# DCC-motor.net
KiCad netlist of a schematic drawn in EAGLE
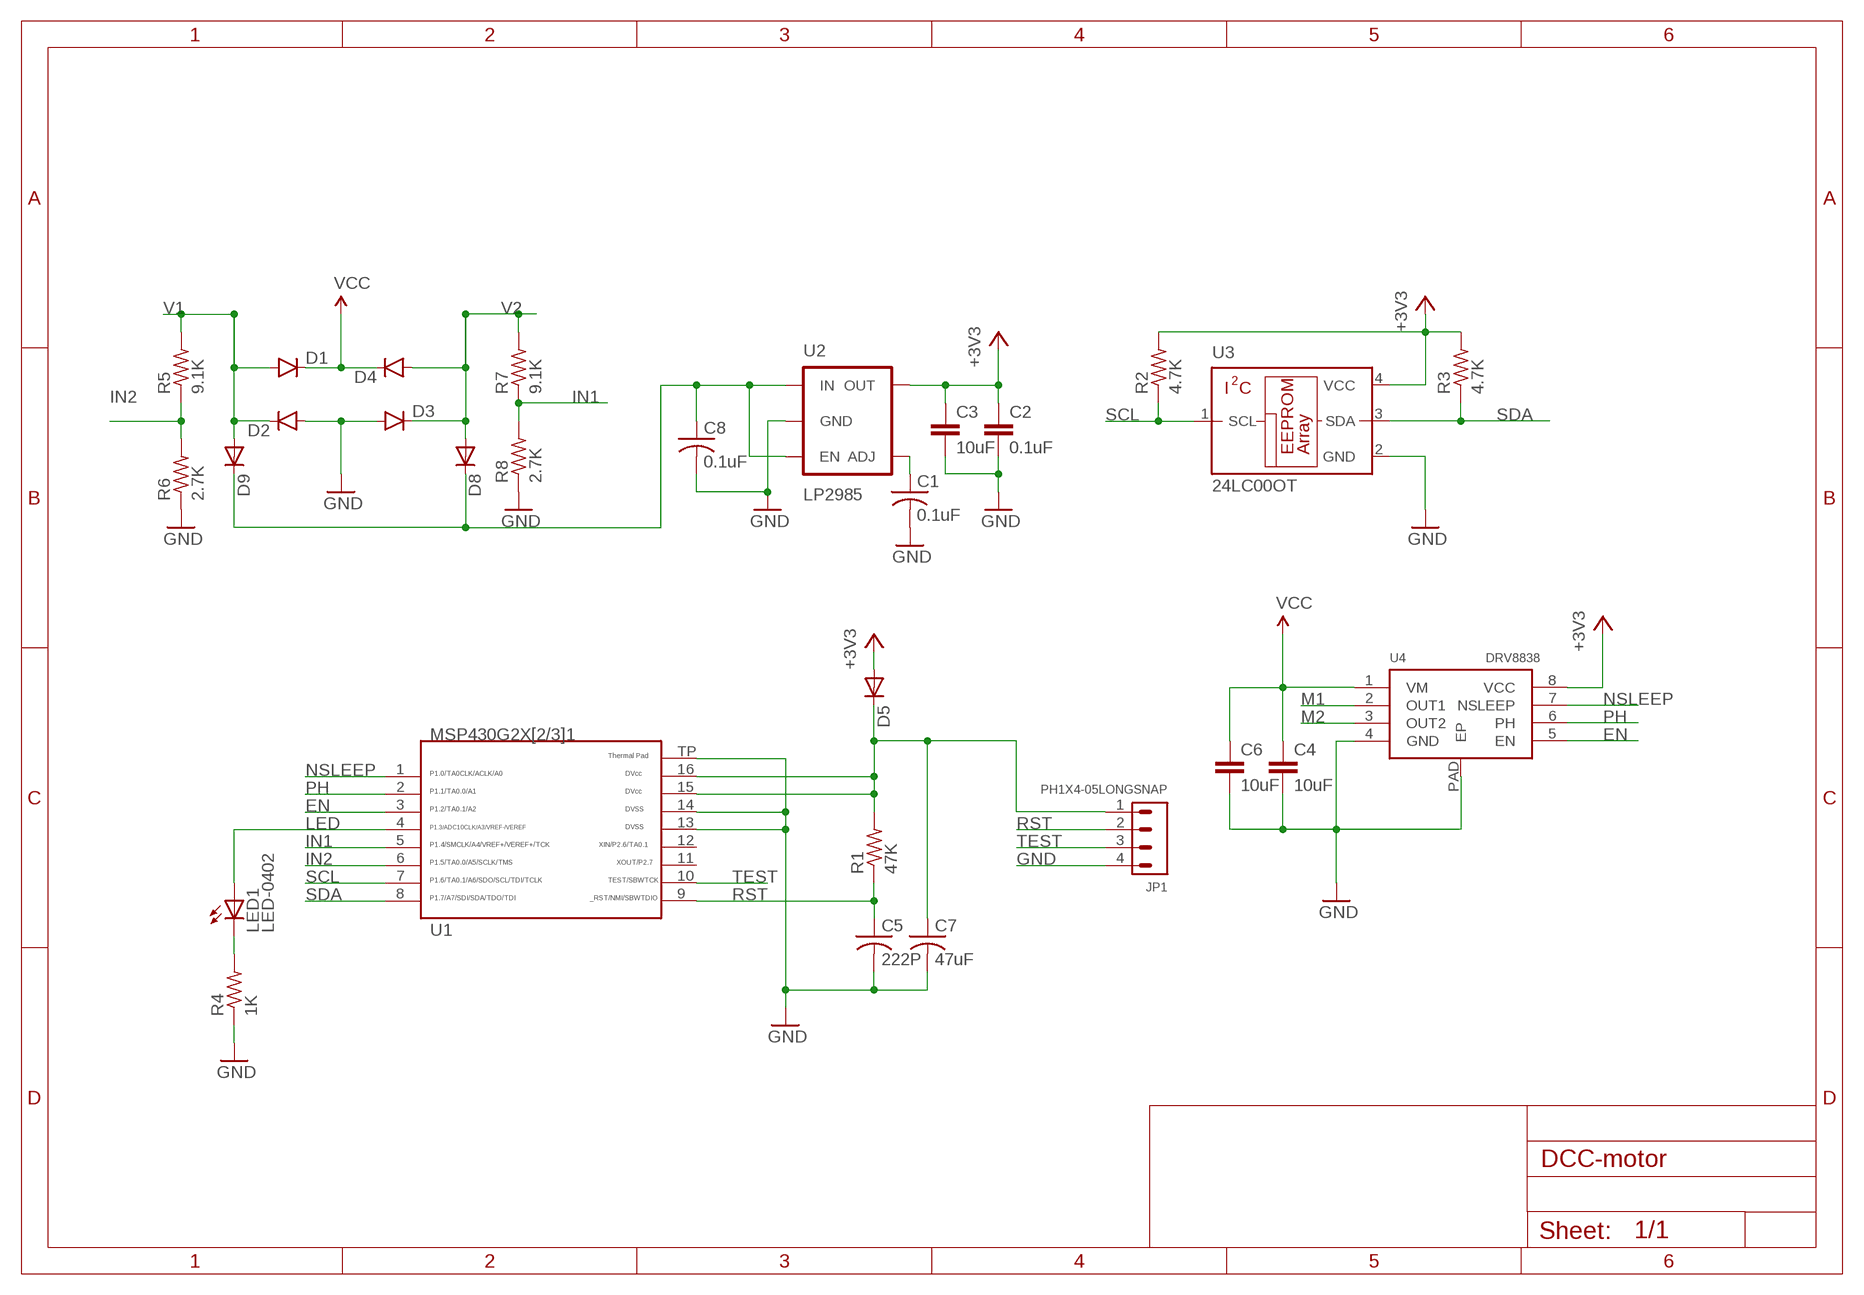
[diagram p0: schematic, sheet 1]

(export (version "E")
  (design (tool "Eeschema 10.0.6"))
  (components
    (comp (ref "C1")
      (value "0.1uF")
      (footprint "eagle-import:C0402")
      (libsource (lib "eagle-import") (part "C-USC0402"))
    )
    (comp (ref "C2")
      (value "0.1uF")
      (footprint "eagle-import:0603-CAP")
      (libsource (lib "eagle-import") (part "CAP0603-CAP"))
    )
    (comp (ref "C3")
      (value "10uF")
      (footprint "eagle-import:0603-CAP")
      (libsource (lib "eagle-import") (part "CAP0603-CAP"))
    )
    (comp (ref "C4")
      (value "10uF")
      (footprint "eagle-import:0603-CAP")
      (libsource (lib "eagle-import") (part "CAP0603-CAP"))
    )
    (comp (ref "C5")
      (value "222P")
      (footprint "eagle-import:C0402")
      (libsource (lib "eagle-import") (part "C-USC0402"))
    )
    (comp (ref "C6")
      (value "10uF")
      (footprint "eagle-import:0603-CAP")
      (libsource (lib "eagle-import") (part "CAP0603-CAP"))
    )
    (comp (ref "C7")
      (value "47uF")
      (footprint "eagle-import:C0402")
      (libsource (lib "eagle-import") (part "C-USC0402"))
    )
    (comp (ref "C8")
      (value "0.1uF")
      (footprint "eagle-import:C0402")
      (libsource (lib "eagle-import") (part "C-USC0402"))
    )
    (comp (ref "D1")
      (value "DIODESOD123")
      (footprint "eagle-import:SOD-123")
      (libsource (lib "eagle-import") (part "DIODESOD123"))
    )
    (comp (ref "D2")
      (value "DIODESOD123")
      (footprint "eagle-import:SOD-123")
      (libsource (lib "eagle-import") (part "DIODESOD123"))
    )
    (comp (ref "D3")
      (value "DIODESOD123")
      (footprint "eagle-import:SOD-123")
      (libsource (lib "eagle-import") (part "DIODESOD123"))
    )
    (comp (ref "D4")
      (value "DIODESOD123")
      (footprint "eagle-import:SOD-123")
      (libsource (lib "eagle-import") (part "DIODESOD123"))
    )
    (comp (ref "D5")
      (value "DIODE-SOD523")
      (footprint "eagle-import:SOD523")
      (libsource (lib "eagle-import") (part "DIODE-SOD523"))
    )
    (comp (ref "D8")
      (value "DIODE-SOD523")
      (footprint "eagle-import:SOD523")
      (libsource (lib "eagle-import") (part "DIODE-SOD523"))
    )
    (comp (ref "D9")
      (value "DIODE-SOD523")
      (footprint "eagle-import:SOD523")
      (libsource (lib "eagle-import") (part "DIODE-SOD523"))
    )
    (comp (ref "JP1")
      (value "PH1X4-05LONGSNAP")
      (footprint "eagle-import:PHLS005-1-4")
      (libsource (lib "eagle-import") (part "PH1X4-05LONGSNAP"))
    )
    (comp (ref "LED1")
      (value "LED-0402")
      (footprint "eagle-import:0402-LED")
      (libsource (lib "eagle-import") (part "LED-0402"))
    )
    (comp (ref "R1")
      (value "47K")
      (footprint "eagle-import:R0402")
      (libsource (lib "eagle-import") (part "R-US_R0402"))
    )
    (comp (ref "R2")
      (value "4.7K")
      (footprint "eagle-import:R0402")
      (libsource (lib "eagle-import") (part "R-US_R0402"))
    )
    (comp (ref "R3")
      (value "4.7K")
      (footprint "eagle-import:R0402")
      (libsource (lib "eagle-import") (part "R-US_R0402"))
    )
    (comp (ref "R4")
      (value "1K")
      (footprint "eagle-import:R0402")
      (libsource (lib "eagle-import") (part "R-US_R0402"))
    )
    (comp (ref "R5")
      (value "9.1K")
      (footprint "eagle-import:R0402")
      (libsource (lib "eagle-import") (part "R-US_R0402"))
    )
    (comp (ref "R6")
      (value "2.7K")
      (footprint "eagle-import:R0402")
      (libsource (lib "eagle-import") (part "R-US_R0402"))
    )
    (comp (ref "R7")
      (value "9.1K")
      (footprint "eagle-import:R0402")
      (libsource (lib "eagle-import") (part "R-US_R0402"))
    )
    (comp (ref "R8")
      (value "2.7K")
      (footprint "eagle-import:R0402")
      (libsource (lib "eagle-import") (part "R-US_R0402"))
    )
    (comp (ref "U1")
      (value "G2X[2/3]1---RSA16")
      (footprint "eagle-import:RSA16")
      (libsource (lib "eagle-import") (part "G2X[2/3]1---RSA16"))
    )
    (comp (ref "U2")
      (value "LP2985")
      (footprint "eagle-import:SOT23-5")
      (libsource (lib "eagle-import") (part "AP2202-ADJ"))
    )
    (comp (ref "U3")
      (value "24LC00OT")
      (footprint "eagle-import:SOT23-5L")
      (fields (field (name "MF") "MICROCHIP") (field (name "MPN") "24LC00T-I/OT"))
      (libsource (lib "eagle-import") (part "2400OTLC"))
    )
    (comp (ref "U4")
      (value "DRV8838")
      (footprint "eagle-import:WSON-8-PAD")
      (libsource (lib "eagle-import") (part "DRV8838"))
    )
  )
  (nets
    (net (code "1") (name "+3V3") (class "Default")
      (node (ref "C2") (pin "1") (pinfunction "1_1") (pintype "passive"))
      (node (ref "C3") (pin "1") (pinfunction "1_1") (pintype "passive"))
      (node (ref "D5") (pin "A") (pinfunction "A_A") (pintype "passive"))
      (node (ref "R2") (pin "2") (pinfunction "2_2") (pintype "passive"))
      (node (ref "R3") (pin "2") (pinfunction "2_2") (pintype "passive"))
      (node (ref "U2") (pin "5") (pinfunction "OUT_5") (pintype "passive"))
      (node (ref "U3") (pin "4") (pinfunction "VCC_4") (pintype "power_in"))
      (node (ref "U4") (pin "8") (pinfunction "VCC_8") (pintype "bidirectional"))
    )
    (net (code "2") (name "/EN") (class "Default")
      (node (ref "U1") (pin "3") (pinfunction "3_3") (pintype "bidirectional"))
      (node (ref "U4") (pin "5") (pinfunction "EN_5") (pintype "bidirectional"))
    )
    (net (code "3") (name "/IN1") (class "Default")
      (node (ref "R7") (pin "1") (pinfunction "1_1") (pintype "passive"))
      (node (ref "R8") (pin "2") (pinfunction "2_2") (pintype "passive"))
      (node (ref "U1") (pin "5") (pinfunction "5_5") (pintype "bidirectional"))
    )
    (net (code "4") (name "/IN2") (class "Default")
      (node (ref "R5") (pin "1") (pinfunction "1_1") (pintype "passive"))
      (node (ref "R6") (pin "2") (pinfunction "2_2") (pintype "passive"))
      (node (ref "U1") (pin "6") (pinfunction "6_6") (pintype "bidirectional"))
    )
    (net (code "5") (name "/LED") (class "Default")
      (node (ref "LED1") (pin "A") (pinfunction "A_A") (pintype "passive"))
      (node (ref "U1") (pin "4") (pinfunction "4_4") (pintype "bidirectional"))
    )
    (net (code "6") (name "/M1") (class "Default")
      (node (ref "U4") (pin "2") (pinfunction "OUT1_2") (pintype "bidirectional"))
    )
    (net (code "7") (name "/M2") (class "Default")
      (node (ref "U4") (pin "3") (pinfunction "OUT2_3") (pintype "bidirectional"))
    )
    (net (code "8") (name "/NSLEEP") (class "Default")
      (node (ref "U1") (pin "1") (pinfunction "1_1") (pintype "bidirectional"))
      (node (ref "U4") (pin "7") (pinfunction "NSLEEP_7") (pintype "bidirectional"))
    )
    (net (code "9") (name "/PH") (class "Default")
      (node (ref "U1") (pin "2") (pinfunction "2_2") (pintype "bidirectional"))
      (node (ref "U4") (pin "6") (pinfunction "PH_6") (pintype "bidirectional"))
    )
    (net (code "10") (name "/RST") (class "Default")
      (node (ref "C5") (pin "1") (pinfunction "1_1") (pintype "passive"))
      (node (ref "JP1") (pin "2") (pinfunction "2_2") (pintype "bidirectional"))
      (node (ref "R1") (pin "1") (pinfunction "1_1") (pintype "passive"))
      (node (ref "U1") (pin "9") (pinfunction "9_9") (pintype "bidirectional"))
    )
    (net (code "11") (name "/SCL") (class "Default")
      (node (ref "R2") (pin "1") (pinfunction "1_1") (pintype "passive"))
      (node (ref "U1") (pin "7") (pinfunction "7_7") (pintype "bidirectional"))
      (node (ref "U3") (pin "1") (pinfunction "SCL_1") (pintype "input"))
    )
    (net (code "12") (name "/SDA") (class "Default")
      (node (ref "R3") (pin "1") (pinfunction "1_1") (pintype "passive"))
      (node (ref "U1") (pin "8") (pinfunction "8_8") (pintype "bidirectional"))
      (node (ref "U3") (pin "3") (pinfunction "SDA_3") (pintype "bidirectional"))
    )
    (net (code "13") (name "/TEST") (class "Default")
      (node (ref "JP1") (pin "3") (pinfunction "3_3") (pintype "bidirectional"))
      (node (ref "U1") (pin "10") (pinfunction "10_10") (pintype "bidirectional"))
    )
    (net (code "14") (name "/V1") (class "Default")
      (node (ref "D1") (pin "A") (pinfunction "A_A") (pintype "passive"))
      (node (ref "D2") (pin "C") (pinfunction "C_C") (pintype "passive"))
      (node (ref "D9") (pin "A") (pinfunction "A_A") (pintype "passive"))
      (node (ref "R5") (pin "2") (pinfunction "2_2") (pintype "passive"))
    )
    (net (code "15") (name "/V2") (class "Default")
      (node (ref "D3") (pin "C") (pinfunction "C_C") (pintype "passive"))
      (node (ref "D4") (pin "A") (pinfunction "A_A") (pintype "passive"))
      (node (ref "D8") (pin "A") (pinfunction "A_A") (pintype "passive"))
      (node (ref "R7") (pin "2") (pinfunction "2_2") (pintype "passive"))
    )
    (net (code "16") (name "GND") (class "Default")
      (node (ref "C1") (pin "2") (pinfunction "2_2") (pintype "passive"))
      (node (ref "C2") (pin "2") (pinfunction "2_2") (pintype "passive"))
      (node (ref "C3") (pin "2") (pinfunction "2_2") (pintype "passive"))
      (node (ref "C4") (pin "2") (pinfunction "2_2") (pintype "passive"))
      (node (ref "C5") (pin "2") (pinfunction "2_2") (pintype "passive"))
      (node (ref "C6") (pin "2") (pinfunction "2_2") (pintype "passive"))
      (node (ref "C7") (pin "2") (pinfunction "2_2") (pintype "passive"))
      (node (ref "C8") (pin "2") (pinfunction "2_2") (pintype "passive"))
      (node (ref "D2") (pin "A") (pinfunction "A_A") (pintype "passive"))
      (node (ref "D3") (pin "A") (pinfunction "A_A") (pintype "passive"))
      (node (ref "JP1") (pin "4") (pinfunction "4_4") (pintype "bidirectional"))
      (node (ref "R4") (pin "1") (pinfunction "1_1") (pintype "passive"))
      (node (ref "R6") (pin "1") (pinfunction "1_1") (pintype "passive"))
      (node (ref "R8") (pin "1") (pinfunction "1_1") (pintype "passive"))
      (node (ref "U1") (pin "13") (pinfunction "13_13") (pintype "bidirectional"))
      (node (ref "U1") (pin "14") (pinfunction "14_14") (pintype "bidirectional"))
      (node (ref "U1") (pin "TP") (pinfunction "TP_TP") (pintype "bidirectional"))
      (node (ref "U2") (pin "2") (pinfunction "GND_2") (pintype "input"))
      (node (ref "U3") (pin "2") (pinfunction "GND_2") (pintype "power_in"))
      (node (ref "U4") (pin "4") (pinfunction "GND_4") (pintype "bidirectional"))
      (node (ref "U4") (pin "PAD") (pinfunction "EP_PAD") (pintype "bidirectional"))
    )
    (net (code "17") (name "Net-(C7-Pad1)") (class "Default")
      (node (ref "C7") (pin "1") (pinfunction "1_1") (pintype "passive"))
      (node (ref "D5") (pin "C") (pinfunction "C_C") (pintype "passive"))
      (node (ref "JP1") (pin "1") (pinfunction "1_1") (pintype "bidirectional"))
      (node (ref "R1") (pin "2") (pinfunction "2_2") (pintype "passive"))
      (node (ref "U1") (pin "15") (pinfunction "15_15") (pintype "bidirectional"))
      (node (ref "U1") (pin "16") (pinfunction "16_16") (pintype "bidirectional"))
    )
    (net (code "18") (name "Net-(LED1-PadC)") (class "Default")
      (node (ref "LED1") (pin "C") (pinfunction "C_C") (pintype "passive"))
      (node (ref "R4") (pin "2") (pinfunction "2_2") (pintype "passive"))
    )
    (net (code "19") (name "Net-(U2-ADJ)") (class "Default")
      (node (ref "C1") (pin "1") (pinfunction "1_1") (pintype "passive"))
      (node (ref "U2") (pin "4") (pinfunction "ADJ_4") (pintype "input"))
    )
    (net (code "20") (name "Net-(U2-EN)") (class "Default")
      (node (ref "C8") (pin "1") (pinfunction "1_1") (pintype "passive"))
      (node (ref "D8") (pin "C") (pinfunction "C_C") (pintype "passive"))
      (node (ref "D9") (pin "C") (pinfunction "C_C") (pintype "passive"))
      (node (ref "U2") (pin "1") (pinfunction "IN_1") (pintype "input"))
      (node (ref "U2") (pin "3") (pinfunction "EN_3") (pintype "input"))
    )
    (net (code "21") (name "VCC") (class "Default")
      (node (ref "C4") (pin "1") (pinfunction "1_1") (pintype "passive"))
      (node (ref "C6") (pin "1") (pinfunction "1_1") (pintype "passive"))
      (node (ref "D1") (pin "C") (pinfunction "C_C") (pintype "passive"))
      (node (ref "D4") (pin "C") (pinfunction "C_C") (pintype "passive"))
      (node (ref "U4") (pin "1") (pinfunction "VM_1") (pintype "bidirectional"))
    )
    (net (code "22") (name "unconnected-(U1-Pad11)") (class "Default")
      (node (ref "U1") (pin "11") (pinfunction "11_11") (pintype "bidirectional"))
    )
    (net (code "23") (name "unconnected-(U1-Pad12)") (class "Default")
      (node (ref "U1") (pin "12") (pinfunction "12_12") (pintype "bidirectional"))
    )
  )
)
